# 907_Controller_Original_-_With_Errors.net
KiCad netlist of a schematic drawn in Altium Designer
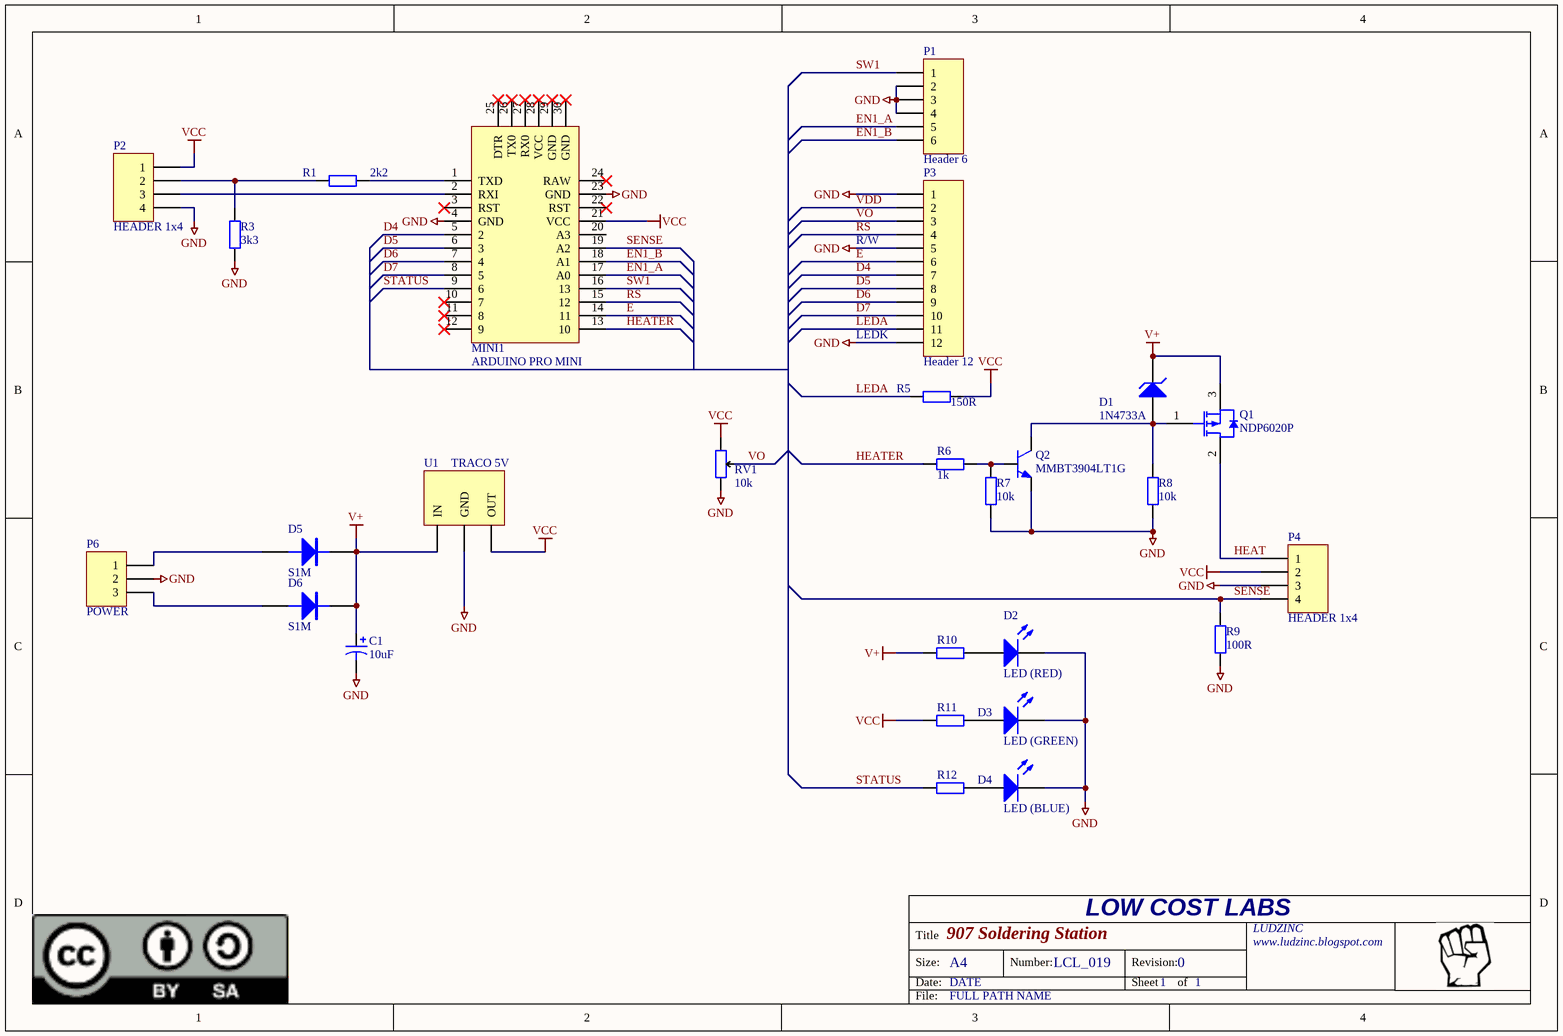
[diagram p0: 907 Controller (Original - With Errors).SchDoc]

(export (version "E")
  (design (tool "Eeschema 10.0.6"))
  (components
    (comp (ref "C1")
      (value "10uF")
      (footprint "CAPACITOR 12.5X20")
      (description "Polarized Capacitor (Radial)")
      (fields (field (name "LCSC PART NO.") "C190964"))
      (libsource (lib "Miscellaneous Devices") (part "Cap Pol1"))
    )
    (comp (ref "D1")
      (value "1N4733A")
      (footprint "DO-41")
      (description "1N4733A 5V ZENER DO-41")
      (libsource (lib "EnvNode") (part "DO-41"))
    )
    (comp (ref "D2")
      (value "LED (RED)")
      (footprint "LED(3D) 3MM VERTICAL (RED)")
      (description "3mm RED LED")
      (fields (field (name "MOUSER PART NO.") "604-WP132XIT") (field (name "FARNELL PART NO.") "1003393"))
      (libsource (lib "NASCO") (part "LED 3mm RED"))
    )
    (comp (ref "D3")
      (value "LED (GREEN)")
      (footprint "LED(3D) 3MM VERTICAL (GREEN)")
      (description "3mm RED LED")
      (fields (field (name "MOUSER PART NO.") "604-WP132XIT") (field (name "FARNELL PART NO.") "1003393"))
      (libsource (lib "NASCO") (part "LED 3mm RED"))
    )
    (comp (ref "D4")
      (value "LED (BLUE)")
      (footprint "LED(3D) 3MM VERTICAL (GREEN)")
      (description "3mm RED LED")
      (fields (field (name "MOUSER PART NO.") "604-WP132XIT") (field (name "FARNELL PART NO.") "1003393"))
      (libsource (lib "NASCO") (part "LED 3mm RED"))
    )
    (comp (ref "D5")
      (value "S1M")
      (footprint "DO-214AC")
      (description "DIODE, POWER")
      (fields (field (name "MOUSER PART NO.") "821-S1M") (field (name "FARNELL PART NO.") "9843841"))
      (libsource (lib "NASCO") (part "DIODE S1M (DO-214AC)"))
    )
    (comp (ref "D6")
      (value "S1M")
      (footprint "DO-214AC")
      (description "DIODE, POWER")
      (fields (field (name "MOUSER PART NO.") "821-S1M") (field (name "FARNELL PART NO.") "9843841"))
      (libsource (lib "NASCO") (part "DIODE S1M (DO-214AC)"))
    )
    (comp (ref "MINI1")
      (value "ARDUINO PRO MINI")
      (footprint "LowCostLabs:ARDUINO PRO MINI")
      (libsource (lib "EletroSketch") (part "ARDUINO PRO MINI"))
    )
    (comp (ref "P1")
      (value "Header 6")
      (footprint "HEADER 1x6")
      (description "Header, 6-Pin")
      (fields (field (name "PUBLISHER") "Altium Limited"))
      (libsource (lib "907 Controller") (part "Header 6"))
    )
    (comp (ref "P2") (value "HEADER 1x4") (footprint "HEADER 1x4") (libsource (lib "") (part "HEADER 1x4_1")))
    (comp (ref "P3")
      (value "Header 12")
      (footprint "HEADER 1x12")
      (description "Header, 12-Pin")
      (fields (field (name "PUBLISHER") "Altium Limited"))
      (libsource (lib "907 Controller") (part "Header 12"))
    )
    (comp (ref "P4")
      (value "HEADER 1x4")
      (footprint "HEADER 1x4")
      (libsource (lib "907 Power Supply") (part "HEADER 1x4"))
    )
    (comp (ref "P6")
      (value "POWER")
      (footprint "power")
      (description "Header, 3 Pin")
      (fields (field (name "MANUFACTURER") "FCI") (field (name "MANUFACTURER PART NO.") "68020-102"))
      (libsource (lib "NASCO") (part "Header 3"))
    )
    (comp (ref "Q1")
      (value "NDP6020P")
      (footprint "TO-220AB - RIGHT ANGLE")
      (description "Trans MOSFET P-CH 20V 24A TO-220AB NDP6020P")
      (libsource (lib "NASCO") (part "NDP6020P"))
    )
    (comp (ref "Q2")
      (value "MMBT3904LT1G")
      (footprint "SOT-23")
      (libsource (lib "907 Controller") (part "NPN"))
    )
    (comp (ref "R1")
      (value "2k2")
      (footprint "RESISTOR 0805")
      (description "Resistor")
      (fields (field (name "PUBLISHER") "Altium Limited"))
      (libsource (lib "") (part "Res2_1"))
    )
    (comp (ref "R3")
      (value "3k3")
      (footprint "RESISTOR 0805")
      (description "Resistor")
      (fields (field (name "PUBLISHER") "Altium Limited"))
      (libsource (lib "Miscellaneous Devices") (part "Res2"))
    )
    (comp (ref "R5")
      (value "150R")
      (footprint "RESISTOR 0805")
      (description "Resistor")
      (fields (field (name "PUBLISHER") "Altium Limited"))
      (libsource (lib "") (part "Res2_2"))
    )
    (comp (ref "R6")
      (value "1k")
      (footprint "RESISTOR 0805")
      (description "Resistor")
      (fields (field (name "PUBLISHER") "Altium Limited"))
      (libsource (lib "") (part "Res2_1"))
    )
    (comp (ref "R7")
      (value "10k")
      (footprint "RESISTOR 0805")
      (description "Resistor")
      (fields (field (name "PUBLISHER") "Altium Limited"))
      (libsource (lib "Miscellaneous Devices") (part "Res2"))
    )
    (comp (ref "R8")
      (value "10k")
      (footprint "RESISTOR 0805")
      (description "Resistor")
      (fields (field (name "PUBLISHER") "Altium Limited"))
      (libsource (lib "Miscellaneous Devices") (part "Res2"))
    )
    (comp (ref "R9")
      (value "100R")
      (footprint "RESISTOR 0805")
      (description "Resistor")
      (fields (field (name "PUBLISHER") "Altium Limited"))
      (libsource (lib "Miscellaneous Devices") (part "Res2"))
    )
    (comp (ref "R10")
      (value "~")
      (footprint "RESISTOR 0805")
      (description "Resistor")
      (fields (field (name "PUBLISHER") "Altium Limited"))
      (libsource (lib "") (part "Res2_1"))
    )
    (comp (ref "R11")
      (value "~")
      (footprint "RESISTOR 0805")
      (description "Resistor")
      (fields (field (name "PUBLISHER") "Altium Limited"))
      (libsource (lib "") (part "Res2_1"))
    )
    (comp (ref "R12")
      (value "~")
      (footprint "RESISTOR 0805")
      (description "Resistor")
      (fields (field (name "PUBLISHER") "Altium Limited"))
      (libsource (lib "") (part "Res2_1"))
    )
    (comp (ref "RV1") (value "10k") (footprint "TRIMPOT") (libsource (lib "907 Controller") (part "TRIMMER")))
    (comp (ref "U1")
      (value "TRACO 5V")
      (footprint "TRACO TSR 1-2450")
      (description "TRACO BUCK 1-2450 MODULE (5V)")
      (libsource (lib "907 Power Supply") (part "TRACO 1-2450"))
    )
  )
  (nets
    (net (code "1") (name "/D4") (class "Default")
      (node (ref "MINI1") (pin "5") (pinfunction "2_5") (pintype "passive"))
      (node (ref "P3") (pin "7") (pinfunction "7_7") (pintype "passive"))
    )
    (net (code "2") (name "/D5") (class "Default")
      (node (ref "MINI1") (pin "6") (pinfunction "3_6") (pintype "passive"))
      (node (ref "P3") (pin "8") (pinfunction "8_8") (pintype "passive"))
    )
    (net (code "3") (name "/D6") (class "Default")
      (node (ref "MINI1") (pin "7") (pinfunction "4_7") (pintype "passive"))
      (node (ref "P3") (pin "9") (pinfunction "9_9") (pintype "passive"))
    )
    (net (code "4") (name "/D7") (class "Default")
      (node (ref "MINI1") (pin "8") (pinfunction "5_8") (pintype "passive"))
      (node (ref "P3") (pin "10") (pinfunction "10_10") (pintype "passive"))
    )
    (net (code "5") (name "/E") (class "Default")
      (node (ref "MINI1") (pin "14") (pinfunction "11_14") (pintype "passive"))
      (node (ref "P3") (pin "6") (pinfunction "6_6") (pintype "passive"))
    )
    (net (code "6") (name "/EN1_A") (class "Default")
      (node (ref "MINI1") (pin "17") (pinfunction "A0_17") (pintype "passive"))
      (node (ref "P1") (pin "5") (pinfunction "5_5") (pintype "passive"))
    )
    (net (code "7") (name "/EN1_B") (class "Default")
      (node (ref "MINI1") (pin "18") (pinfunction "A1_18") (pintype "passive"))
      (node (ref "P1") (pin "6") (pinfunction "6_6") (pintype "passive"))
    )
    (net (code "8") (name "/HEAT") (class "Default")
      (node (ref "P4") (pin "1") (pinfunction "1_1") (pintype "passive"))
      (node (ref "Q1") (pin "2") (pinfunction "D_2") (pintype "passive"))
    )
    (net (code "9") (name "/HEATER") (class "Default")
      (node (ref "MINI1") (pin "13") (pinfunction "10_13") (pintype "passive"))
      (node (ref "R6") (pin "1") (pinfunction "1_1") (pintype "passive"))
    )
    (net (code "10") (name "/LEDA") (class "Default")
      (node (ref "P3") (pin "11") (pinfunction "11_11") (pintype "passive"))
      (node (ref "R5") (pin "2") (pinfunction "2_2") (pintype "passive"))
    )
    (net (code "11") (name "/RS") (class "Default")
      (node (ref "MINI1") (pin "15") (pinfunction "12_15") (pintype "passive"))
      (node (ref "P3") (pin "4") (pinfunction "4_4") (pintype "passive"))
    )
    (net (code "12") (name "/SENSE") (class "Default")
      (node (ref "MINI1") (pin "19") (pinfunction "A2_19") (pintype "passive"))
      (node (ref "P4") (pin "4") (pinfunction "4_4") (pintype "passive"))
      (node (ref "R9") (pin "1") (pinfunction "1_1") (pintype "passive"))
    )
    (net (code "13") (name "/STATUS") (class "Default")
      (node (ref "MINI1") (pin "9") (pinfunction "6_9") (pintype "passive"))
      (node (ref "R12") (pin "1") (pinfunction "1_1") (pintype "passive"))
    )
    (net (code "14") (name "/SW1") (class "Default")
      (node (ref "MINI1") (pin "16") (pinfunction "13_16") (pintype "passive"))
      (node (ref "P1") (pin "1") (pinfunction "1_1") (pintype "passive"))
    )
    (net (code "15") (name "/VDD") (class "Default")
      (node (ref "P3") (pin "2") (pinfunction "2_2") (pintype "passive"))
    )
    (net (code "16") (name "/VO") (class "Default")
      (node (ref "P3") (pin "3") (pinfunction "3_3") (pintype "passive"))
      (node (ref "RV1") (pin "2") (pinfunction "2_2") (pintype "passive"))
    )
    (net (code "17") (name "GND") (class "Default")
      (node (ref "C1") (pin "2") (pinfunction "2_2") (pintype "passive"))
      (node (ref "D2") (pin "2") (pinfunction "K_2") (pintype "passive"))
      (node (ref "D3") (pin "2") (pinfunction "K_2") (pintype "passive"))
      (node (ref "D4") (pin "2") (pinfunction "K_2") (pintype "passive"))
      (node (ref "MINI1") (pin "23") (pinfunction "GND_23") (pintype "passive"))
      (node (ref "MINI1") (pin "4") (pinfunction "GND_4") (pintype "passive"))
      (node (ref "P1") (pin "2") (pinfunction "2_2") (pintype "passive"))
      (node (ref "P1") (pin "3") (pinfunction "3_3") (pintype "passive"))
      (node (ref "P1") (pin "4") (pinfunction "4_4") (pintype "passive"))
      (node (ref "P2") (pin "4") (pinfunction "4_4") (pintype "passive"))
      (node (ref "P3") (pin "1") (pinfunction "1_1") (pintype "passive"))
      (node (ref "P3") (pin "12") (pinfunction "12_12") (pintype "passive"))
      (node (ref "P3") (pin "5") (pinfunction "5_5") (pintype "passive"))
      (node (ref "P4") (pin "3") (pinfunction "3_3") (pintype "passive"))
      (node (ref "P6") (pin "2") (pinfunction "2_2") (pintype "passive"))
      (node (ref "Q2") (pin "2") (pinfunction "E_2") (pintype "passive"))
      (node (ref "R3") (pin "2") (pinfunction "2_2") (pintype "passive"))
      (node (ref "R7") (pin "2") (pinfunction "2_2") (pintype "passive"))
      (node (ref "R8") (pin "2") (pinfunction "2_2") (pintype "passive"))
      (node (ref "R9") (pin "2") (pinfunction "2_2") (pintype "passive"))
      (node (ref "RV1") (pin "1") (pinfunction "1_1") (pintype "passive"))
      (node (ref "U1") (pin "2") (pinfunction "GND_2") (pintype "passive"))
    )
    (net (code "18") (name "Net-(D1-A)") (class "Default")
      (node (ref "D1") (pin "2") (pinfunction "A_2") (pintype "passive"))
      (node (ref "Q1") (pin "1") (pinfunction "G_1") (pintype "passive"))
      (node (ref "Q2") (pin "3") (pinfunction "C_3") (pintype "passive"))
      (node (ref "R8") (pin "1") (pinfunction "1_1") (pintype "passive"))
    )
    (net (code "19") (name "Net-(D2-A)") (class "Default")
      (node (ref "D2") (pin "1") (pinfunction "A_1") (pintype "passive"))
      (node (ref "R10") (pin "2") (pinfunction "2_2") (pintype "passive"))
    )
    (net (code "20") (name "Net-(D3-A)") (class "Default")
      (node (ref "D3") (pin "1") (pinfunction "A_1") (pintype "passive"))
      (node (ref "R11") (pin "2") (pinfunction "2_2") (pintype "passive"))
    )
    (net (code "21") (name "Net-(D4-A)") (class "Default")
      (node (ref "D4") (pin "1") (pinfunction "A_1") (pintype "passive"))
      (node (ref "R12") (pin "2") (pinfunction "2_2") (pintype "passive"))
    )
    (net (code "22") (name "Net-(D5-A)") (class "Default")
      (node (ref "D5") (pin "1") (pinfunction "A_1") (pintype "passive"))
      (node (ref "P6") (pin "1") (pinfunction "1_1") (pintype "passive"))
    )
    (net (code "23") (name "Net-(D6-A)") (class "Default")
      (node (ref "D6") (pin "1") (pinfunction "A_1") (pintype "passive"))
      (node (ref "P6") (pin "3") (pinfunction "3_3") (pintype "passive"))
    )
    (net (code "24") (name "Net-(MINI1-RXI)") (class "Default")
      (node (ref "MINI1") (pin "2") (pinfunction "RXI_2") (pintype "passive"))
      (node (ref "P2") (pin "3") (pinfunction "3_3") (pintype "passive"))
    )
    (net (code "25") (name "Net-(MINI1-TXD)") (class "Default")
      (node (ref "MINI1") (pin "1") (pinfunction "TXD_1") (pintype "passive"))
      (node (ref "R1") (pin "2") (pinfunction "2_2") (pintype "passive"))
    )
    (net (code "26") (name "Net-(P2-Pad2)") (class "Default")
      (node (ref "P2") (pin "2") (pinfunction "2_2") (pintype "passive"))
      (node (ref "R1") (pin "1") (pinfunction "1_1") (pintype "passive"))
      (node (ref "R3") (pin "1") (pinfunction "1_1") (pintype "passive"))
    )
    (net (code "27") (name "Net-(Q2-B)") (class "Default")
      (node (ref "Q2") (pin "1") (pinfunction "B_1") (pintype "passive"))
      (node (ref "R6") (pin "2") (pinfunction "2_2") (pintype "passive"))
      (node (ref "R7") (pin "1") (pinfunction "1_1") (pintype "passive"))
    )
    (net (code "28") (name "V+") (class "Default")
      (node (ref "C1") (pin "1") (pinfunction "1_1") (pintype "passive"))
      (node (ref "D1") (pin "1") (pinfunction "K_1") (pintype "passive"))
      (node (ref "D5") (pin "2") (pinfunction "K_2") (pintype "passive"))
      (node (ref "D6") (pin "2") (pinfunction "K_2") (pintype "passive"))
      (node (ref "Q1") (pin "3") (pinfunction "S_3") (pintype "passive"))
      (node (ref "R10") (pin "1") (pinfunction "1_1") (pintype "passive"))
      (node (ref "U1") (pin "1") (pinfunction "IN_1") (pintype "passive"))
    )
    (net (code "29") (name "VCC") (class "Default")
      (node (ref "MINI1") (pin "21") (pinfunction "VCC_21") (pintype "passive"))
      (node (ref "P2") (pin "1") (pinfunction "1_1") (pintype "passive"))
      (node (ref "P4") (pin "2") (pinfunction "2_2") (pintype "passive"))
      (node (ref "R11") (pin "1") (pinfunction "1_1") (pintype "passive"))
      (node (ref "R5") (pin "1") (pinfunction "1_1") (pintype "passive"))
      (node (ref "RV1") (pin "3") (pinfunction "3_3") (pintype "passive"))
      (node (ref "U1") (pin "3") (pinfunction "OUT_3") (pintype "passive"))
    )
    (net (code "30") (name "unconnected-(MINI1-7-Pad10)") (class "Default")
      (node (ref "MINI1") (pin "10") (pinfunction "7_10") (pintype "passive+no_connect"))
    )
    (net (code "31") (name "unconnected-(MINI1-8-Pad11)") (class "Default")
      (node (ref "MINI1") (pin "11") (pinfunction "8_11") (pintype "passive+no_connect"))
    )
    (net (code "32") (name "unconnected-(MINI1-9-Pad12)") (class "Default")
      (node (ref "MINI1") (pin "12") (pinfunction "9_12") (pintype "passive+no_connect"))
    )
    (net (code "33") (name "unconnected-(MINI1-A3-Pad20)") (class "Default")
      (node (ref "MINI1") (pin "20") (pinfunction "A3_20") (pintype "passive"))
    )
    (net (code "34") (name "unconnected-(MINI1-DTR-Pad25)") (class "Default")
      (node (ref "MINI1") (pin "25") (pinfunction "DTR_25") (pintype "passive+no_connect"))
    )
    (net (code "35") (name "unconnected-(MINI1-GND-Pad29)") (class "Default")
      (node (ref "MINI1") (pin "29") (pinfunction "GND_29") (pintype "passive+no_connect"))
    )
    (net (code "36") (name "unconnected-(MINI1-GND-Pad30)") (class "Default")
      (node (ref "MINI1") (pin "30") (pinfunction "GND_30") (pintype "passive+no_connect"))
    )
    (net (code "37") (name "unconnected-(MINI1-RAW-Pad24)") (class "Default")
      (node (ref "MINI1") (pin "24") (pinfunction "RAW_24") (pintype "passive+no_connect"))
    )
    (net (code "38") (name "unconnected-(MINI1-RST-Pad3)") (class "Default")
      (node (ref "MINI1") (pin "3") (pinfunction "RST_3") (pintype "passive+no_connect"))
    )
    (net (code "39") (name "unconnected-(MINI1-RST-Pad22)") (class "Default")
      (node (ref "MINI1") (pin "22") (pinfunction "RST_22") (pintype "passive+no_connect"))
    )
    (net (code "40") (name "unconnected-(MINI1-RX0-Pad27)") (class "Default")
      (node (ref "MINI1") (pin "27") (pinfunction "RX0_27") (pintype "passive+no_connect"))
    )
    (net (code "41") (name "unconnected-(MINI1-TX0-Pad26)") (class "Default")
      (node (ref "MINI1") (pin "26") (pinfunction "TX0_26") (pintype "passive+no_connect"))
    )
    (net (code "42") (name "unconnected-(MINI1-VCC-Pad28)") (class "Default")
      (node (ref "MINI1") (pin "28") (pinfunction "VCC_28") (pintype "passive+no_connect"))
    )
  )
)
